# QDRII_power.net
KiCad netlist of a schematic drawn in Altium Designer
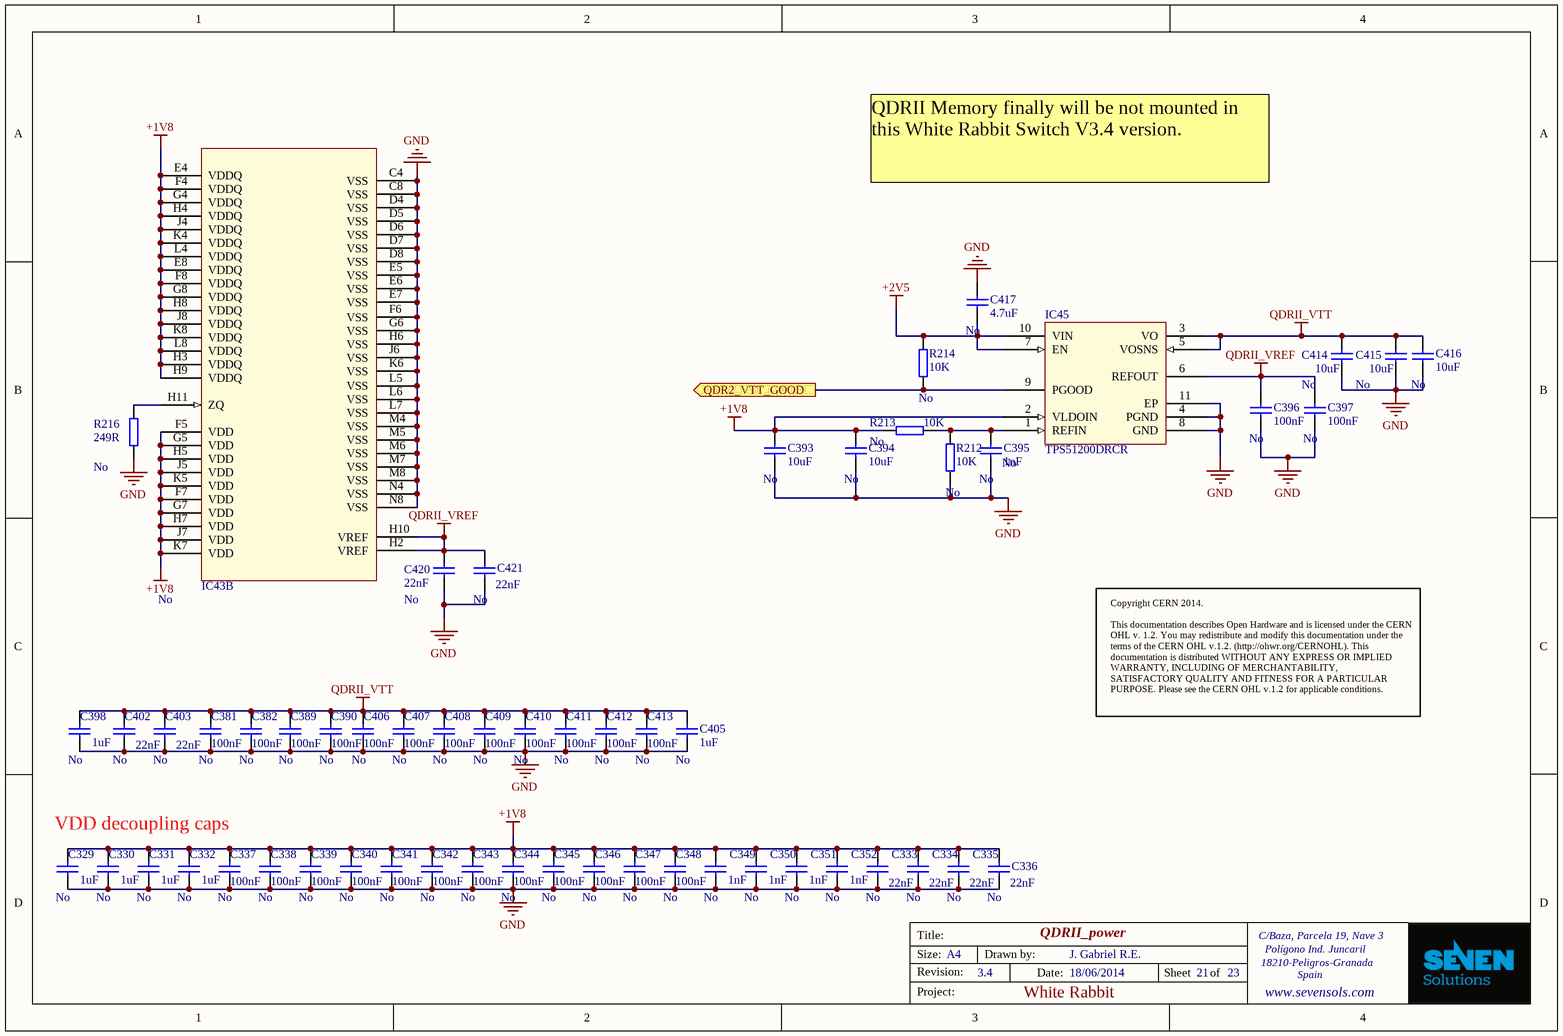
[diagram p0: QDRII_power.SchDoc]

(export (version "E")
  (design (tool "Eeschema 10.0.6"))
  (components
    (comp (ref "C329")
      (value "1uF")
      (footprint "CC1005-0402")
      (description "Capacitor")
      (fields
        (field (name "TOLERANCE") "±10%")
        (field (name "VOLTAGE") "16V")
        (field (name "MOUNTED") "No")
        (field (name "PUBLISHER") "Altium Limited")
      )
      (libsource (lib "wr_switch") (part "Cap"))
    )
    (comp (ref "C330")
      (value "1uF")
      (footprint "CC1005-0402")
      (description "Capacitor")
      (fields
        (field (name "TOLERANCE") "±10%")
        (field (name "VOLTAGE") "16V")
        (field (name "MOUNTED") "No")
        (field (name "PUBLISHER") "Altium Limited")
      )
      (libsource (lib "wr_switch") (part "Cap"))
    )
    (comp (ref "C331")
      (value "1uF")
      (footprint "CC1005-0402")
      (description "Capacitor")
      (fields
        (field (name "TOLERANCE") "±10%")
        (field (name "VOLTAGE") "16V")
        (field (name "MOUNTED") "No")
        (field (name "PUBLISHER") "Altium Limited")
      )
      (libsource (lib "wr_switch") (part "Cap"))
    )
    (comp (ref "C332")
      (value "1uF")
      (footprint "CC1005-0402")
      (description "Capacitor")
      (fields
        (field (name "TOLERANCE") "±10%")
        (field (name "VOLTAGE") "16V")
        (field (name "MOUNTED") "No")
        (field (name "PUBLISHER") "Altium Limited")
      )
      (libsource (lib "wr_switch") (part "Cap"))
    )
    (comp (ref "C333")
      (value "22nF")
      (footprint "CC1005-0402")
      (description "Capacitor")
      (fields
        (field (name "TOLERANCE") "±10%")
        (field (name "VOLTAGE") "25V")
        (field (name "MOUNTED") "No")
        (field (name "PUBLISHER") "Altium Limited")
      )
      (libsource (lib "wr_switch") (part "Cap"))
    )
    (comp (ref "C334")
      (value "22nF")
      (footprint "CC1005-0402")
      (description "Capacitor")
      (fields
        (field (name "TOLERANCE") "±10%")
        (field (name "VOLTAGE") "25V")
        (field (name "MOUNTED") "No")
        (field (name "PUBLISHER") "Altium Limited")
      )
      (libsource (lib "wr_switch") (part "Cap"))
    )
    (comp (ref "C335")
      (value "22nF")
      (footprint "CC1005-0402")
      (description "Capacitor")
      (fields
        (field (name "TOLERANCE") "±10%")
        (field (name "VOLTAGE") "25V")
        (field (name "MOUNTED") "No")
        (field (name "PUBLISHER") "Altium Limited")
      )
      (libsource (lib "wr_switch") (part "Cap"))
    )
    (comp (ref "C336")
      (value "22nF")
      (footprint "CC1005-0402")
      (description "Capacitor")
      (fields
        (field (name "TOLERANCE") "±10%")
        (field (name "VOLTAGE") "25V")
        (field (name "MOUNTED") "No")
        (field (name "PUBLISHER") "Altium Limited")
      )
      (libsource (lib "wr_switch") (part "Cap"))
    )
    (comp (ref "C337")
      (value "100nF")
      (footprint "CC1005-0402")
      (description "Capacitor")
      (fields
        (field (name "TOLERANCE") "±10%")
        (field (name "VOLTAGE") "16V")
        (field (name "MOUNTED") "No")
        (field (name "PUBLISHER") "Altium Limited")
      )
      (libsource (lib "wr_switch") (part "Cap"))
    )
    (comp (ref "C338")
      (value "100nF")
      (footprint "CC1005-0402")
      (description "Capacitor")
      (fields
        (field (name "TOLERANCE") "±10%")
        (field (name "VOLTAGE") "16V")
        (field (name "MOUNTED") "No")
        (field (name "PUBLISHER") "Altium Limited")
      )
      (libsource (lib "wr_switch") (part "Cap"))
    )
    (comp (ref "C339")
      (value "100nF")
      (footprint "CC1005-0402")
      (description "Capacitor")
      (fields
        (field (name "TOLERANCE") "±10%")
        (field (name "VOLTAGE") "16V")
        (field (name "MOUNTED") "No")
        (field (name "PUBLISHER") "Altium Limited")
      )
      (libsource (lib "wr_switch") (part "Cap"))
    )
    (comp (ref "C340")
      (value "100nF")
      (footprint "CC1005-0402")
      (description "Capacitor")
      (fields
        (field (name "TOLERANCE") "±10%")
        (field (name "VOLTAGE") "16V")
        (field (name "MOUNTED") "No")
        (field (name "PUBLISHER") "Altium Limited")
      )
      (libsource (lib "wr_switch") (part "Cap"))
    )
    (comp (ref "C341")
      (value "100nF")
      (footprint "CC1005-0402")
      (description "Capacitor")
      (fields
        (field (name "TOLERANCE") "±10%")
        (field (name "VOLTAGE") "16V")
        (field (name "MOUNTED") "No")
        (field (name "PUBLISHER") "Altium Limited")
      )
      (libsource (lib "wr_switch") (part "Cap"))
    )
    (comp (ref "C342")
      (value "100nF")
      (footprint "CC1005-0402")
      (description "Capacitor")
      (fields
        (field (name "TOLERANCE") "±10%")
        (field (name "VOLTAGE") "16V")
        (field (name "MOUNTED") "No")
        (field (name "PUBLISHER") "Altium Limited")
      )
      (libsource (lib "wr_switch") (part "Cap"))
    )
    (comp (ref "C343")
      (value "100nF")
      (footprint "CC1005-0402")
      (description "Capacitor")
      (fields
        (field (name "TOLERANCE") "±10%")
        (field (name "VOLTAGE") "16V")
        (field (name "MOUNTED") "No")
        (field (name "PUBLISHER") "Altium Limited")
      )
      (libsource (lib "wr_switch") (part "Cap"))
    )
    (comp (ref "C344")
      (value "100nF")
      (footprint "CC1005-0402")
      (description "Capacitor")
      (fields
        (field (name "TOLERANCE") "±10%")
        (field (name "VOLTAGE") "16V")
        (field (name "MOUNTED") "No")
        (field (name "PUBLISHER") "Altium Limited")
      )
      (libsource (lib "wr_switch") (part "Cap"))
    )
    (comp (ref "C345")
      (value "100nF")
      (footprint "CC1005-0402")
      (description "Capacitor")
      (fields
        (field (name "TOLERANCE") "±10%")
        (field (name "VOLTAGE") "16V")
        (field (name "MOUNTED") "No")
        (field (name "PUBLISHER") "Altium Limited")
      )
      (libsource (lib "wr_switch") (part "Cap"))
    )
    (comp (ref "C346")
      (value "100nF")
      (footprint "CC1005-0402")
      (description "Capacitor")
      (fields
        (field (name "TOLERANCE") "±10%")
        (field (name "VOLTAGE") "16V")
        (field (name "MOUNTED") "No")
        (field (name "PUBLISHER") "Altium Limited")
      )
      (libsource (lib "wr_switch") (part "Cap"))
    )
    (comp (ref "C347")
      (value "100nF")
      (footprint "CC1005-0402")
      (description "Capacitor")
      (fields
        (field (name "TOLERANCE") "±10%")
        (field (name "VOLTAGE") "16V")
        (field (name "MOUNTED") "No")
        (field (name "PUBLISHER") "Altium Limited")
      )
      (libsource (lib "wr_switch") (part "Cap"))
    )
    (comp (ref "C348")
      (value "100nF")
      (footprint "CC1005-0402")
      (description "Capacitor")
      (fields
        (field (name "TOLERANCE") "±10%")
        (field (name "VOLTAGE") "16V")
        (field (name "MOUNTED") "No")
        (field (name "PUBLISHER") "Altium Limited")
      )
      (libsource (lib "wr_switch") (part "Cap"))
    )
    (comp (ref "C349")
      (value "1nF")
      (footprint "CC1005-0402")
      (description "Capacitor")
      (fields
        (field (name "TOLERANCE") "±10%")
        (field (name "VOLTAGE") "25V")
        (field (name "MOUNTED") "No")
        (field (name "PUBLISHER") "Altium Limited")
      )
      (libsource (lib "wr_switch") (part "Cap"))
    )
    (comp (ref "C350")
      (value "1nF")
      (footprint "CC1005-0402")
      (description "Capacitor")
      (fields
        (field (name "TOLERANCE") "±10%")
        (field (name "VOLTAGE") "25V")
        (field (name "MOUNTED") "No")
        (field (name "PUBLISHER") "Altium Limited")
      )
      (libsource (lib "wr_switch") (part "Cap"))
    )
    (comp (ref "C351")
      (value "1nF")
      (footprint "CC1005-0402")
      (description "Capacitor")
      (fields
        (field (name "TOLERANCE") "±10%")
        (field (name "VOLTAGE") "25V")
        (field (name "MOUNTED") "No")
        (field (name "PUBLISHER") "Altium Limited")
      )
      (libsource (lib "wr_switch") (part "Cap"))
    )
    (comp (ref "C352")
      (value "1nF")
      (footprint "CC1005-0402")
      (description "Capacitor")
      (fields
        (field (name "TOLERANCE") "±10%")
        (field (name "VOLTAGE") "25V")
        (field (name "MOUNTED") "No")
        (field (name "PUBLISHER") "Altium Limited")
      )
      (libsource (lib "wr_switch") (part "Cap"))
    )
    (comp (ref "C381")
      (value "100nF")
      (footprint "CC1005-0402")
      (description "Capacitor")
      (fields
        (field (name "TOLERANCE") "±10%")
        (field (name "VOLTAGE") "16V")
        (field (name "MOUNTED") "No")
        (field (name "PUBLISHER") "Altium Limited")
      )
      (libsource (lib "wr_switch") (part "Cap"))
    )
    (comp (ref "C382")
      (value "100nF")
      (footprint "CC1005-0402")
      (description "Capacitor")
      (fields
        (field (name "TOLERANCE") "±10%")
        (field (name "VOLTAGE") "16V")
        (field (name "MOUNTED") "No")
        (field (name "PUBLISHER") "Altium Limited")
      )
      (libsource (lib "wr_switch") (part "Cap"))
    )
    (comp (ref "C389")
      (value "100nF")
      (footprint "CC1005-0402")
      (description "Capacitor")
      (fields
        (field (name "TOLERANCE") "±10%")
        (field (name "VOLTAGE") "16V")
        (field (name "MOUNTED") "No")
        (field (name "PUBLISHER") "Altium Limited")
      )
      (libsource (lib "wr_switch") (part "Cap"))
    )
    (comp (ref "C390")
      (value "100nF")
      (footprint "CC1005-0402")
      (description "Capacitor")
      (fields
        (field (name "TOLERANCE") "±10%")
        (field (name "VOLTAGE") "16V")
        (field (name "MOUNTED") "No")
        (field (name "PUBLISHER") "Altium Limited")
      )
      (libsource (lib "wr_switch") (part "Cap"))
    )
    (comp (ref "C393")
      (value "10uF")
      (footprint "CC1608-0603")
      (description "Capacitor")
      (fields
        (field (name "TOLERANCE") "±20%")
        (field (name "VOLTAGE") "6.3V")
        (field (name "MOUNTED") "No")
        (field (name "PUBLISHER") "Altium Limited")
      )
      (libsource (lib "wr_switch") (part "Cap"))
    )
    (comp (ref "C394")
      (value "10uF")
      (footprint "CC1608-0603")
      (description "Capacitor")
      (fields
        (field (name "TOLERANCE") "±20%")
        (field (name "VOLTAGE") "6.3V")
        (field (name "MOUNTED") "No")
        (field (name "PUBLISHER") "Altium Limited")
      )
      (libsource (lib "wr_switch") (part "Cap"))
    )
    (comp (ref "C395")
      (value "1nF")
      (footprint "CC1005-0402")
      (description "Capacitor")
      (fields
        (field (name "TOLERANCE") "±10%")
        (field (name "VOLTAGE") "25V")
        (field (name "MOUNTED") "No")
        (field (name "PUBLISHER") "Altium Limited")
      )
      (libsource (lib "wr_switch") (part "Cap"))
    )
    (comp (ref "C396")
      (value "100nF")
      (footprint "CC1005-0402")
      (description "Capacitor")
      (fields
        (field (name "TOLERANCE") "±10%")
        (field (name "VOLTAGE") "16V")
        (field (name "MOUNTED") "No")
        (field (name "PUBLISHER") "Altium Limited")
      )
      (libsource (lib "wr_switch") (part "Cap"))
    )
    (comp (ref "C397")
      (value "100nF")
      (footprint "CC1005-0402")
      (description "Capacitor")
      (fields
        (field (name "TOLERANCE") "±10%")
        (field (name "VOLTAGE") "16V")
        (field (name "MOUNTED") "No")
        (field (name "PUBLISHER") "Altium Limited")
      )
      (libsource (lib "wr_switch") (part "Cap"))
    )
    (comp (ref "C398")
      (value "1uF")
      (footprint "CC1005-0402")
      (description "Capacitor")
      (fields
        (field (name "TOLERANCE") "±10%")
        (field (name "VOLTAGE") "16V")
        (field (name "MOUNTED") "No")
        (field (name "PUBLISHER") "Altium Limited")
      )
      (libsource (lib "wr_switch") (part "Cap"))
    )
    (comp (ref "C402")
      (value "22nF")
      (footprint "CC1005-0402")
      (description "Capacitor")
      (fields
        (field (name "TOLERANCE") "±10%")
        (field (name "VOLTAGE") "25V")
        (field (name "MOUNTED") "No")
        (field (name "PUBLISHER") "Altium Limited")
      )
      (libsource (lib "wr_switch") (part "Cap"))
    )
    (comp (ref "C403")
      (value "22nF")
      (footprint "CC1005-0402")
      (description "Capacitor")
      (fields
        (field (name "TOLERANCE") "±10%")
        (field (name "VOLTAGE") "25V")
        (field (name "MOUNTED") "No")
        (field (name "PUBLISHER") "Altium Limited")
      )
      (libsource (lib "wr_switch") (part "Cap"))
    )
    (comp (ref "C405")
      (value "1uF")
      (footprint "CC1005-0402")
      (description "Capacitor")
      (fields
        (field (name "TOLERANCE") "±10%")
        (field (name "VOLTAGE") "16V")
        (field (name "MOUNTED") "No")
        (field (name "PUBLISHER") "Altium Limited")
      )
      (libsource (lib "wr_switch") (part "Cap"))
    )
    (comp (ref "C406")
      (value "100nF")
      (footprint "CC1005-0402")
      (description "Capacitor")
      (fields
        (field (name "TOLERANCE") "±10%")
        (field (name "VOLTAGE") "16V")
        (field (name "MOUNTED") "No")
        (field (name "PUBLISHER") "Altium Limited")
      )
      (libsource (lib "wr_switch") (part "Cap"))
    )
    (comp (ref "C407")
      (value "100nF")
      (footprint "CC1005-0402")
      (description "Capacitor")
      (fields
        (field (name "TOLERANCE") "±10%")
        (field (name "VOLTAGE") "16V")
        (field (name "MOUNTED") "No")
        (field (name "PUBLISHER") "Altium Limited")
      )
      (libsource (lib "wr_switch") (part "Cap"))
    )
    (comp (ref "C408")
      (value "100nF")
      (footprint "CC1005-0402")
      (description "Capacitor")
      (fields
        (field (name "TOLERANCE") "±10%")
        (field (name "VOLTAGE") "16V")
        (field (name "MOUNTED") "No")
        (field (name "PUBLISHER") "Altium Limited")
      )
      (libsource (lib "wr_switch") (part "Cap"))
    )
    (comp (ref "C409")
      (value "100nF")
      (footprint "CC1005-0402")
      (description "Capacitor")
      (fields
        (field (name "TOLERANCE") "±10%")
        (field (name "VOLTAGE") "16V")
        (field (name "MOUNTED") "No")
        (field (name "PUBLISHER") "Altium Limited")
      )
      (libsource (lib "wr_switch") (part "Cap"))
    )
    (comp (ref "C410")
      (value "100nF")
      (footprint "CC1005-0402")
      (description "Capacitor")
      (fields
        (field (name "TOLERANCE") "±10%")
        (field (name "VOLTAGE") "16V")
        (field (name "MOUNTED") "No")
        (field (name "PUBLISHER") "Altium Limited")
      )
      (libsource (lib "wr_switch") (part "Cap"))
    )
    (comp (ref "C411")
      (value "100nF")
      (footprint "CC1005-0402")
      (description "Capacitor")
      (fields
        (field (name "TOLERANCE") "±10%")
        (field (name "VOLTAGE") "16V")
        (field (name "MOUNTED") "No")
        (field (name "PUBLISHER") "Altium Limited")
      )
      (libsource (lib "wr_switch") (part "Cap"))
    )
    (comp (ref "C412")
      (value "100nF")
      (footprint "CC1005-0402")
      (description "Capacitor")
      (fields
        (field (name "TOLERANCE") "±10%")
        (field (name "VOLTAGE") "16V")
        (field (name "MOUNTED") "No")
        (field (name "PUBLISHER") "Altium Limited")
      )
      (libsource (lib "wr_switch") (part "Cap"))
    )
    (comp (ref "C413")
      (value "100nF")
      (footprint "CC1005-0402")
      (description "Capacitor")
      (fields
        (field (name "TOLERANCE") "±10%")
        (field (name "VOLTAGE") "16V")
        (field (name "MOUNTED") "No")
        (field (name "PUBLISHER") "Altium Limited")
      )
      (libsource (lib "wr_switch") (part "Cap"))
    )
    (comp (ref "C414")
      (value "10uF")
      (footprint "CC1608-0603")
      (description "Capacitor")
      (fields
        (field (name "TOLERANCE") "±20%")
        (field (name "VOLTAGE") "6.3V")
        (field (name "MOUNTED") "No")
        (field (name "PUBLISHER") "Altium Limited")
      )
      (libsource (lib "wr_switch") (part "Cap"))
    )
    (comp (ref "C415")
      (value "10uF")
      (footprint "CC1608-0603")
      (description "Capacitor")
      (fields
        (field (name "TOLERANCE") "±20%")
        (field (name "VOLTAGE") "6.3V")
        (field (name "MOUNTED") "No")
        (field (name "PUBLISHER") "Altium Limited")
      )
      (libsource (lib "wr_switch") (part "Cap"))
    )
    (comp (ref "C416")
      (value "10uF")
      (footprint "CC1608-0603")
      (description "Capacitor")
      (fields
        (field (name "TOLERANCE") "±20%")
        (field (name "VOLTAGE") "6.3V")
        (field (name "MOUNTED") "No")
        (field (name "PUBLISHER") "Altium Limited")
      )
      (libsource (lib "wr_switch") (part "Cap"))
    )
    (comp (ref "C417")
      (value "4.7uF")
      (footprint "CC1608-0603")
      (description "Capacitor")
      (fields
        (field (name "TOLERANCE") "±10%")
        (field (name "VOLTAGE") "10V")
        (field (name "MOUNTED") "No")
        (field (name "PUBLISHER") "Altium Limited")
      )
      (libsource (lib "wr_switch") (part "Cap"))
    )
    (comp (ref "C420")
      (value "22nF")
      (footprint "CC1005-0402")
      (description "Capacitor")
      (fields
        (field (name "TOLERANCE") "±10%")
        (field (name "VOLTAGE") "25V")
        (field (name "MOUNTED") "No")
        (field (name "PUBLISHER") "Altium Limited")
      )
      (libsource (lib "wr_switch") (part "Cap"))
    )
    (comp (ref "C421")
      (value "22nF")
      (footprint "CC1005-0402")
      (description "Capacitor")
      (fields
        (field (name "TOLERANCE") "±10%")
        (field (name "VOLTAGE") "25V")
        (field (name "MOUNTED") "No")
        (field (name "PUBLISHER") "Altium Limited")
      )
      (libsource (lib "wr_switch") (part "Cap"))
    )
    (comp (ref "IC43")
      (value "CY7C1314KV18-250BZC")
      (footprint "BGA165C100P11X15_1300X1500X140")
      (description "18-Mbit (512Kx36) QDRII SRAM 2-Word Burst Architecture")
      (fields (field (name "MOUNTED") "No"))
      (libsource (lib "wr_switch") (part "CY7C1314CV18"))
    )
    (comp (ref "IC45")
      (value "TPS51200DRCR")
      (footprint "SON50P300X300X100-11N-R175X250")
      (description "Sink/Source DDR Termination Regulator")
      (fields (field (name "MOUNTED") "No"))
      (libsource (lib "wr_switch") (part "TPS51200"))
    )
    (comp (ref "R212")
      (value "10K")
      (footprint "0402")
      (description "SMD Resistor")
      (fields (field (name "TOLERANCE") "±1%") (field (name "MOUNTED") "No") (field (name "Comment") "10k"))
      (libsource (lib "wr_switch") (part "RES_SMD"))
    )
    (comp (ref "R213")
      (value "10K")
      (footprint "0402")
      (description "SMD Resistor")
      (fields (field (name "TOLERANCE") "±1%") (field (name "MOUNTED") "No") (field (name "Comment") "10k"))
      (libsource (lib "wr_switch") (part "RES_SMD"))
    )
    (comp (ref "R214")
      (value "10K")
      (footprint "0402")
      (description "SMD Resistor")
      (fields (field (name "TOLERANCE") "±1%") (field (name "MOUNTED") "No") (field (name "Comment") "10k"))
      (libsource (lib "wr_switch") (part "RES_SMD"))
    )
    (comp (ref "R216")
      (value "249R")
      (footprint "0402")
      (description "SMD Resistor")
      (fields (field (name "TOLERANCE") "±1%") (field (name "MOUNTED") "No"))
      (libsource (lib "wr_switch") (part "RES_SMD"))
    )
  )
  (nets
    (net (code "1") (name "+1V8") (class "Default")
      (node (ref "C329") (pin "2") (pinfunction "2_2") (pintype "passive"))
      (node (ref "C330") (pin "2") (pinfunction "2_2") (pintype "passive"))
      (node (ref "C331") (pin "2") (pinfunction "2_2") (pintype "passive"))
      (node (ref "C332") (pin "2") (pinfunction "2_2") (pintype "passive"))
      (node (ref "C333") (pin "2") (pinfunction "2_2") (pintype "passive"))
      (node (ref "C334") (pin "2") (pinfunction "2_2") (pintype "passive"))
      (node (ref "C335") (pin "2") (pinfunction "2_2") (pintype "passive"))
      (node (ref "C336") (pin "2") (pinfunction "2_2") (pintype "passive"))
      (node (ref "C337") (pin "1") (pinfunction "1_1") (pintype "passive"))
      (node (ref "C338") (pin "1") (pinfunction "1_1") (pintype "passive"))
      (node (ref "C339") (pin "1") (pinfunction "1_1") (pintype "passive"))
      (node (ref "C340") (pin "1") (pinfunction "1_1") (pintype "passive"))
      (node (ref "C341") (pin "1") (pinfunction "1_1") (pintype "passive"))
      (node (ref "C342") (pin "1") (pinfunction "1_1") (pintype "passive"))
      (node (ref "C343") (pin "1") (pinfunction "1_1") (pintype "passive"))
      (node (ref "C344") (pin "1") (pinfunction "1_1") (pintype "passive"))
      (node (ref "C345") (pin "1") (pinfunction "1_1") (pintype "passive"))
      (node (ref "C346") (pin "1") (pinfunction "1_1") (pintype "passive"))
      (node (ref "C347") (pin "1") (pinfunction "1_1") (pintype "passive"))
      (node (ref "C348") (pin "1") (pinfunction "1_1") (pintype "passive"))
      (node (ref "C349") (pin "2") (pinfunction "2_2") (pintype "passive"))
      (node (ref "C350") (pin "2") (pinfunction "2_2") (pintype "passive"))
      (node (ref "C351") (pin "2") (pinfunction "2_2") (pintype "passive"))
      (node (ref "C352") (pin "2") (pinfunction "2_2") (pintype "passive"))
      (node (ref "C393") (pin "2") (pinfunction "2_2") (pintype "passive"))
      (node (ref "C394") (pin "2") (pinfunction "2_2") (pintype "passive"))
      (node (ref "IC43") (pin "E4") (pinfunction "VDDQ_E4") (pintype "power_in"))
      (node (ref "IC43") (pin "E8") (pinfunction "VDDQ_E8") (pintype "power_in"))
      (node (ref "IC43") (pin "F4") (pinfunction "VDDQ_F4") (pintype "power_in"))
      (node (ref "IC43") (pin "F5") (pinfunction "VDD_F5") (pintype "power_in"))
      (node (ref "IC43") (pin "F7") (pinfunction "VDD_F7") (pintype "power_in"))
      (node (ref "IC43") (pin "F8") (pinfunction "VDDQ_F8") (pintype "power_in"))
      (node (ref "IC43") (pin "G4") (pinfunction "VDDQ_G4") (pintype "power_in"))
      (node (ref "IC43") (pin "G5") (pinfunction "VDD_G5") (pintype "power_in"))
      (node (ref "IC43") (pin "G7") (pinfunction "VDD_G7") (pintype "power_in"))
      (node (ref "IC43") (pin "G8") (pinfunction "VDDQ_G8") (pintype "power_in"))
      (node (ref "IC43") (pin "H3") (pinfunction "VDDQ_H3") (pintype "power_in"))
      (node (ref "IC43") (pin "H4") (pinfunction "VDDQ_H4") (pintype "power_in"))
      (node (ref "IC43") (pin "H5") (pinfunction "VDD_H5") (pintype "power_in"))
      (node (ref "IC43") (pin "H7") (pinfunction "VDD_H7") (pintype "power_in"))
      (node (ref "IC43") (pin "H8") (pinfunction "VDDQ_H8") (pintype "power_in"))
      (node (ref "IC43") (pin "H9") (pinfunction "VDDQ_H9") (pintype "power_in"))
      (node (ref "IC43") (pin "J4") (pinfunction "VDDQ_J4") (pintype "power_in"))
      (node (ref "IC43") (pin "J5") (pinfunction "VDD_J5") (pintype "power_in"))
      (node (ref "IC43") (pin "J7") (pinfunction "VDD_J7") (pintype "power_in"))
      (node (ref "IC43") (pin "J8") (pinfunction "VDDQ_J8") (pintype "power_in"))
      (node (ref "IC43") (pin "K4") (pinfunction "VDDQ_K4") (pintype "power_in"))
      (node (ref "IC43") (pin "K5") (pinfunction "VDD_K5") (pintype "power_in"))
      (node (ref "IC43") (pin "K7") (pinfunction "VDD_K7") (pintype "power_in"))
      (node (ref "IC43") (pin "K8") (pinfunction "VDDQ_K8") (pintype "power_in"))
      (node (ref "IC43") (pin "L4") (pinfunction "VDDQ_L4") (pintype "power_in"))
      (node (ref "IC43") (pin "L8") (pinfunction "VDDQ_L8") (pintype "power_in"))
      (node (ref "IC45") (pin "2") (pinfunction "VLDOIN_2") (pintype "input"))
      (node (ref "R213") (pin "2") (pinfunction "2_2") (pintype "passive"))
    )
    (net (code "2") (name "+2V5") (class "Default")
      (node (ref "C417") (pin "1") (pinfunction "1_1") (pintype "passive"))
      (node (ref "IC45") (pin "10") (pinfunction "VIN_10") (pintype "power_in"))
      (node (ref "IC45") (pin "7") (pinfunction "EN_7") (pintype "input"))
      (node (ref "R214") (pin "2") (pinfunction "2_2") (pintype "passive"))
    )
    (net (code "3") (name "/QDR2_VTT_GOOD") (class "Default")
      (node (ref "IC45") (pin "9") (pinfunction "PGOOD_9") (pintype "open_collector"))
      (node (ref "R214") (pin "1") (pinfunction "1_1") (pintype "passive"))
    )
    (net (code "4") (name "GND") (class "Default")
      (node (ref "C329") (pin "1") (pinfunction "1_1") (pintype "passive"))
      (node (ref "C330") (pin "1") (pinfunction "1_1") (pintype "passive"))
      (node (ref "C331") (pin "1") (pinfunction "1_1") (pintype "passive"))
      (node (ref "C332") (pin "1") (pinfunction "1_1") (pintype "passive"))
      (node (ref "C333") (pin "1") (pinfunction "1_1") (pintype "passive"))
      (node (ref "C334") (pin "1") (pinfunction "1_1") (pintype "passive"))
      (node (ref "C335") (pin "1") (pinfunction "1_1") (pintype "passive"))
      (node (ref "C336") (pin "1") (pinfunction "1_1") (pintype "passive"))
      (node (ref "C337") (pin "2") (pinfunction "2_2") (pintype "passive"))
      (node (ref "C338") (pin "2") (pinfunction "2_2") (pintype "passive"))
      (node (ref "C339") (pin "2") (pinfunction "2_2") (pintype "passive"))
      (node (ref "C340") (pin "2") (pinfunction "2_2") (pintype "passive"))
      (node (ref "C341") (pin "2") (pinfunction "2_2") (pintype "passive"))
      (node (ref "C342") (pin "2") (pinfunction "2_2") (pintype "passive"))
      (node (ref "C343") (pin "2") (pinfunction "2_2") (pintype "passive"))
      (node (ref "C344") (pin "2") (pinfunction "2_2") (pintype "passive"))
      (node (ref "C345") (pin "2") (pinfunction "2_2") (pintype "passive"))
      (node (ref "C346") (pin "2") (pinfunction "2_2") (pintype "passive"))
      (node (ref "C347") (pin "2") (pinfunction "2_2") (pintype "passive"))
      (node (ref "C348") (pin "2") (pinfunction "2_2") (pintype "passive"))
      (node (ref "C349") (pin "1") (pinfunction "1_1") (pintype "passive"))
      (node (ref "C350") (pin "1") (pinfunction "1_1") (pintype "passive"))
      (node (ref "C351") (pin "1") (pinfunction "1_1") (pintype "passive"))
      (node (ref "C352") (pin "1") (pinfunction "1_1") (pintype "passive"))
      (node (ref "C381") (pin "2") (pinfunction "2_2") (pintype "passive"))
      (node (ref "C382") (pin "2") (pinfunction "2_2") (pintype "passive"))
      (node (ref "C389") (pin "2") (pinfunction "2_2") (pintype "passive"))
      (node (ref "C390") (pin "2") (pinfunction "2_2") (pintype "passive"))
      (node (ref "C393") (pin "1") (pinfunction "1_1") (pintype "passive"))
      (node (ref "C394") (pin "1") (pinfunction "1_1") (pintype "passive"))
      (node (ref "C395") (pin "1") (pinfunction "1_1") (pintype "passive"))
      (node (ref "C396") (pin "2") (pinfunction "2_2") (pintype "passive"))
      (node (ref "C397") (pin "2") (pinfunction "2_2") (pintype "passive"))
      (node (ref "C398") (pin "1") (pinfunction "1_1") (pintype "passive"))
      (node (ref "C402") (pin "1") (pinfunction "1_1") (pintype "passive"))
      (node (ref "C403") (pin "1") (pinfunction "1_1") (pintype "passive"))
      (node (ref "C405") (pin "1") (pinfunction "1_1") (pintype "passive"))
      (node (ref "C406") (pin "2") (pinfunction "2_2") (pintype "passive"))
      (node (ref "C407") (pin "2") (pinfunction "2_2") (pintype "passive"))
      (node (ref "C408") (pin "2") (pinfunction "2_2") (pintype "passive"))
      (node (ref "C409") (pin "2") (pinfunction "2_2") (pintype "passive"))
      (node (ref "C410") (pin "2") (pinfunction "2_2") (pintype "passive"))
      (node (ref "C411") (pin "2") (pinfunction "2_2") (pintype "passive"))
      (node (ref "C412") (pin "2") (pinfunction "2_2") (pintype "passive"))
      (node (ref "C413") (pin "2") (pinfunction "2_2") (pintype "passive"))
      (node (ref "C414") (pin "1") (pinfunction "1_1") (pintype "passive"))
      (node (ref "C415") (pin "1") (pinfunction "1_1") (pintype "passive"))
      (node (ref "C416") (pin "1") (pinfunction "1_1") (pintype "passive"))
      (node (ref "C417") (pin "2") (pinfunction "2_2") (pintype "passive"))
      (node (ref "C420") (pin "1") (pinfunction "1_1") (pintype "passive"))
      (node (ref "C421") (pin "1") (pinfunction "1_1") (pintype "passive"))
      (node (ref "IC43") (pin "C4") (pinfunction "VSS_C4") (pintype "power_in"))
      (node (ref "IC43") (pin "C8") (pinfunction "VSS_C8") (pintype "power_in"))
      (node (ref "IC43") (pin "D4") (pinfunction "VSS_D4") (pintype "power_in"))
      (node (ref "IC43") (pin "D5") (pinfunction "VSS_D5") (pintype "power_in"))
      (node (ref "IC43") (pin "D6") (pinfunction "VSS_D6") (pintype "power_in"))
      (node (ref "IC43") (pin "D7") (pinfunction "VSS_D7") (pintype "power_in"))
      (node (ref "IC43") (pin "D8") (pinfunction "VSS_D8") (pintype "power_in"))
      (node (ref "IC43") (pin "E5") (pinfunction "VSS_E5") (pintype "power_in"))
      (node (ref "IC43") (pin "E6") (pinfunction "VSS_E6") (pintype "power_in"))
      (node (ref "IC43") (pin "E7") (pinfunction "VSS_E7") (pintype "power_in"))
      (node (ref "IC43") (pin "F6") (pinfunction "VSS_F6") (pintype "power_in"))
      (node (ref "IC43") (pin "G6") (pinfunction "VSS_G6") (pintype "power_in"))
      (node (ref "IC43") (pin "H6") (pinfunction "VSS_H6") (pintype "power_in"))
      (node (ref "IC43") (pin "J6") (pinfunction "VSS_J6") (pintype "power_in"))
      (node (ref "IC43") (pin "K6") (pinfunction "VSS_K6") (pintype "power_in"))
      (node (ref "IC43") (pin "L5") (pinfunction "VSS_L5") (pintype "power_in"))
      (node (ref "IC43") (pin "L6") (pinfunction "VSS_L6") (pintype "power_in"))
      (node (ref "IC43") (pin "L7") (pinfunction "VSS_L7") (pintype "power_in"))
      (node (ref "IC43") (pin "M4") (pinfunction "VSS_M4") (pintype "power_in"))
      (node (ref "IC43") (pin "M5") (pinfunction "VSS_M5") (pintype "power_in"))
      (node (ref "IC43") (pin "M6") (pinfunction "VSS_M6") (pintype "power_in"))
      (node (ref "IC43") (pin "M7") (pinfunction "VSS_M7") (pintype "power_in"))
      (node (ref "IC43") (pin "M8") (pinfunction "VSS_M8") (pintype "power_in"))
      (node (ref "IC43") (pin "N4") (pinfunction "VSS_N4") (pintype "power_in"))
      (node (ref "IC43") (pin "N8") (pinfunction "VSS_N8") (pintype "power_in"))
      (node (ref "IC45") (pin "11") (pinfunction "EP_11") (pintype "power_in"))
      (node (ref "IC45") (pin "4") (pinfunction "PGND_4") (pintype "power_in"))
      (node (ref "IC45") (pin "8") (pinfunction "GND_8") (pintype "power_in"))
      (node (ref "R212") (pin "1") (pinfunction "1_1") (pintype "passive"))
      (node (ref "R216") (pin "1") (pinfunction "1_1") (pintype "passive"))
    )
    (net (code "5") (name "Net-(IC43B-ZQ)") (class "Default")
      (node (ref "IC43") (pin "H11") (pinfunction "ZQ_H11") (pintype "input"))
      (node (ref "R216") (pin "2") (pinfunction "2_2") (pintype "passive"))
    )
    (net (code "6") (name "Net-(IC45-REFIN)") (class "Default")
      (node (ref "C395") (pin "2") (pinfunction "2_2") (pintype "passive"))
      (node (ref "IC45") (pin "1") (pinfunction "REFIN_1") (pintype "input"))
      (node (ref "R212") (pin "2") (pinfunction "2_2") (pintype "passive"))
      (node (ref "R213") (pin "1") (pinfunction "1_1") (pintype "passive"))
    )
    (net (code "7") (name "QDRII_VREF") (class "Default")
      (node (ref "C396") (pin "1") (pinfunction "1_1") (pintype "passive"))
      (node (ref "C397") (pin "1") (pinfunction "1_1") (pintype "passive"))
      (node (ref "C420") (pin "2") (pinfunction "2_2") (pintype "passive"))
      (node (ref "C421") (pin "2") (pinfunction "2_2") (pintype "passive"))
      (node (ref "IC43") (pin "H10") (pinfunction "VREF_H10") (pintype "power_in"))
      (node (ref "IC43") (pin "H2") (pinfunction "VREF_H2") (pintype "power_in"))
      (node (ref "IC45") (pin "6") (pinfunction "REFOUT_6") (pintype "power_in"))
    )
    (net (code "8") (name "QDRII_VTT") (class "Default")
      (node (ref "C381") (pin "1") (pinfunction "1_1") (pintype "passive"))
      (node (ref "C382") (pin "1") (pinfunction "1_1") (pintype "passive"))
      (node (ref "C389") (pin "1") (pinfunction "1_1") (pintype "passive"))
      (node (ref "C390") (pin "1") (pinfunction "1_1") (pintype "passive"))
      (node (ref "C398") (pin "2") (pinfunction "2_2") (pintype "passive"))
      (node (ref "C402") (pin "2") (pinfunction "2_2") (pintype "passive"))
      (node (ref "C403") (pin "2") (pinfunction "2_2") (pintype "passive"))
      (node (ref "C405") (pin "2") (pinfunction "2_2") (pintype "passive"))
      (node (ref "C406") (pin "1") (pinfunction "1_1") (pintype "passive"))
      (node (ref "C407") (pin "1") (pinfunction "1_1") (pintype "passive"))
      (node (ref "C408") (pin "1") (pinfunction "1_1") (pintype "passive"))
      (node (ref "C409") (pin "1") (pinfunction "1_1") (pintype "passive"))
      (node (ref "C410") (pin "1") (pinfunction "1_1") (pintype "passive"))
      (node (ref "C411") (pin "1") (pinfunction "1_1") (pintype "passive"))
      (node (ref "C412") (pin "1") (pinfunction "1_1") (pintype "passive"))
      (node (ref "C413") (pin "1") (pinfunction "1_1") (pintype "passive"))
      (node (ref "C414") (pin "2") (pinfunction "2_2") (pintype "passive"))
      (node (ref "C415") (pin "2") (pinfunction "2_2") (pintype "passive"))
      (node (ref "C416") (pin "2") (pinfunction "2_2") (pintype "passive"))
      (node (ref "IC45") (pin "3") (pinfunction "VO_3") (pintype "power_in"))
      (node (ref "IC45") (pin "5") (pinfunction "VOSNS_5") (pintype "input"))
    )
  )
)
